# Module_Hub.net
KiCad netlist of a schematic drawn in Altium Designer
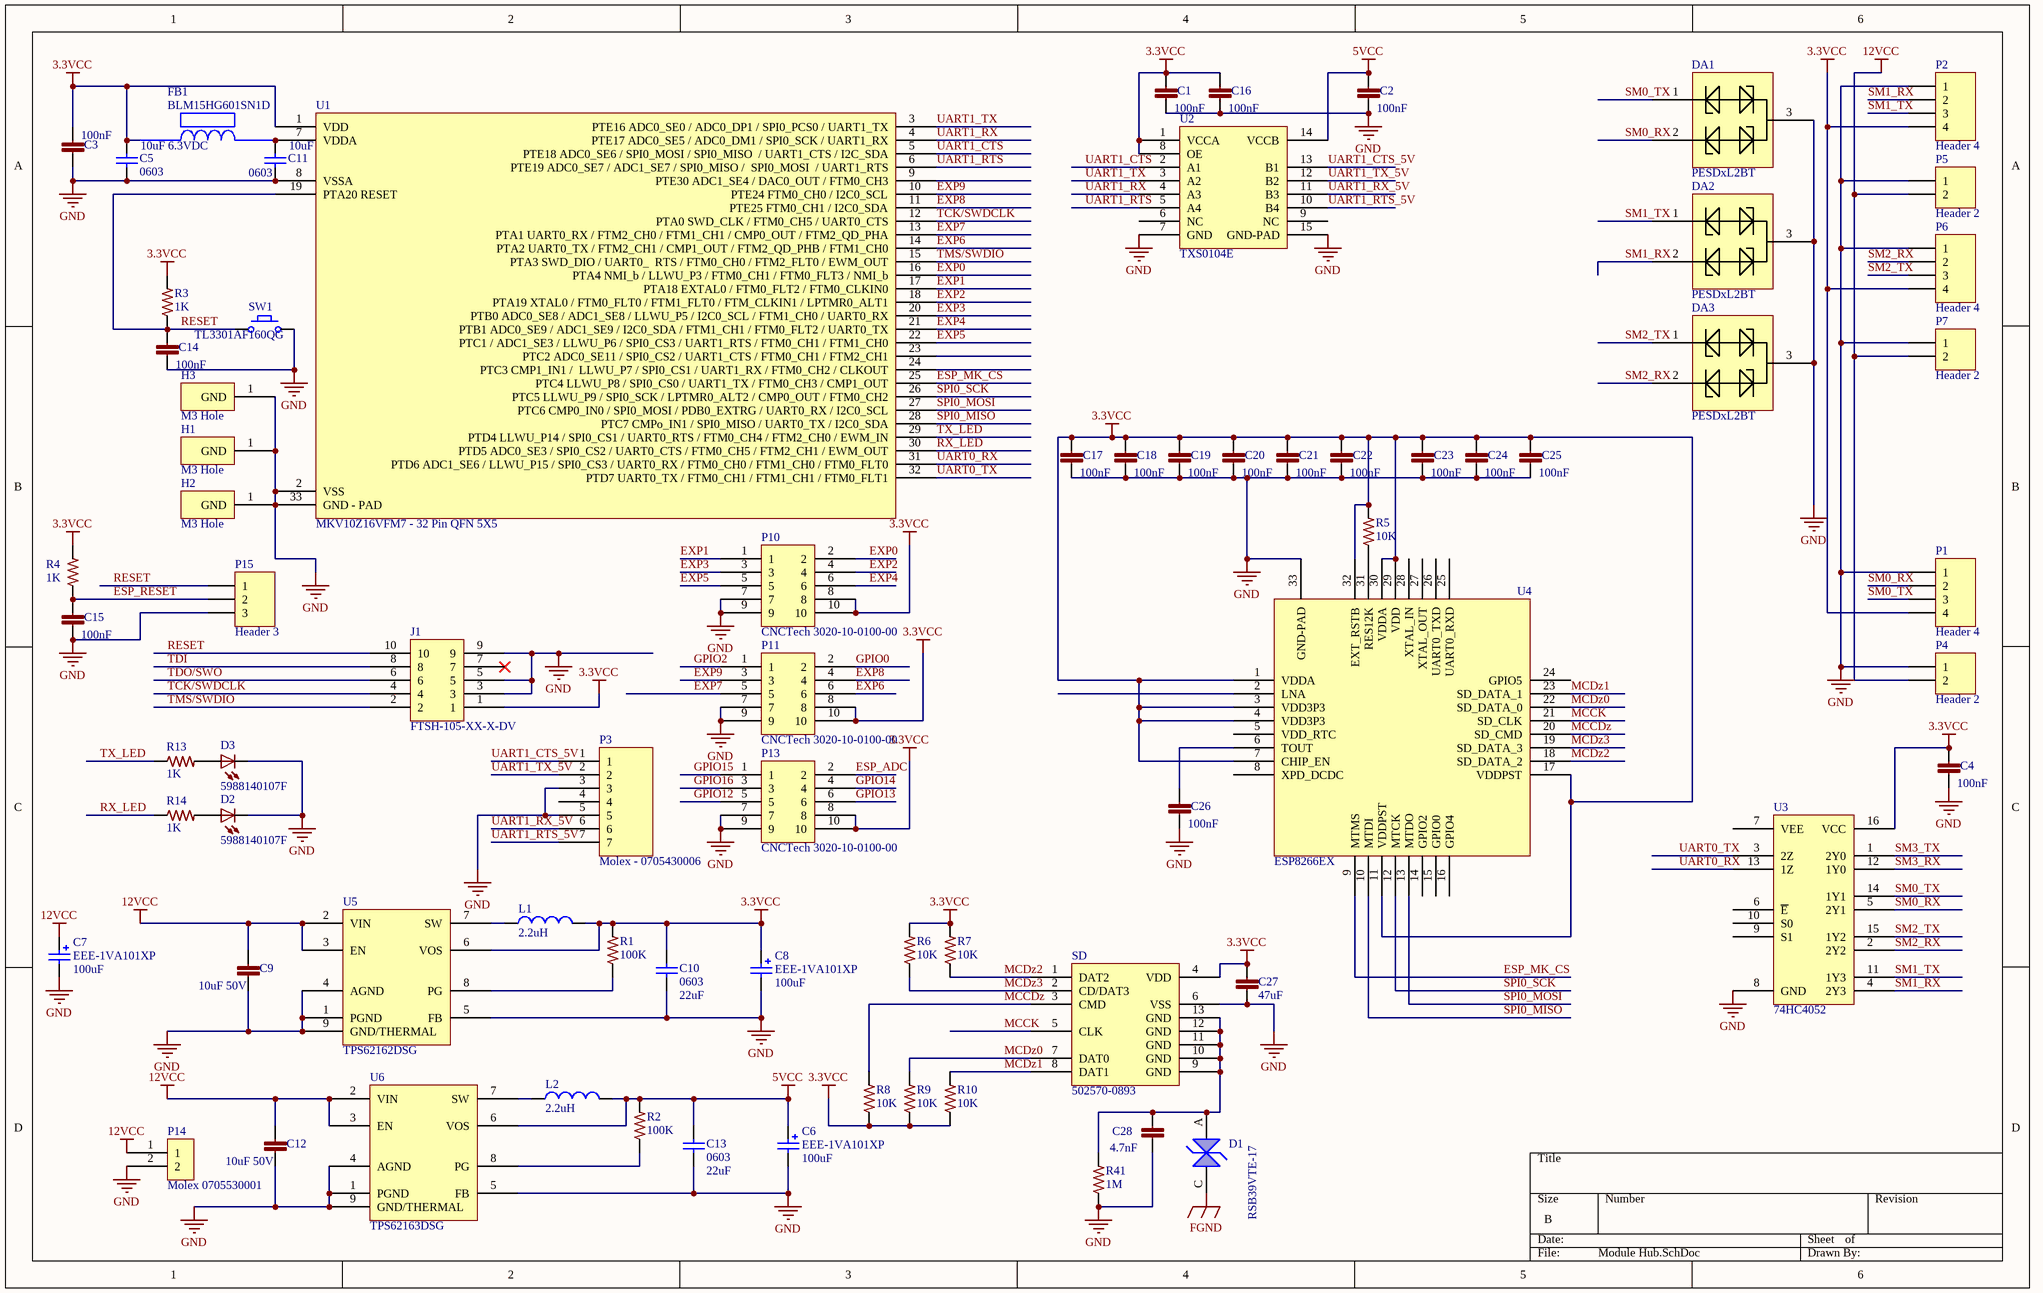
[diagram p0: Module Hub.SchDoc]

(export (version "E")
  (design (tool "Eeschema 10.0.6"))
  (components
    (comp (ref "C1")
      (value "100nF")
      (footprint "C0603")
      (description "CAP CER 0603 100nF 50V 10% X7R")
      (fields
        (field (name "MANUFACTURERPARTNUMBER") "C0603C104K5RACTU")
        (field (name "PUBLISHER") "UltiMachine")
      )
      (libsource (lib "3Delight") (part "C0603C104K5RACTU"))
    )
    (comp (ref "C2")
      (value "100nF")
      (footprint "C0603")
      (description "CAP CER 0603 100nF 50V 10% X7R")
      (fields
        (field (name "MANUFACTURERPARTNUMBER") "C0603C104K5RACTU")
        (field (name "PUBLISHER") "UltiMachine")
      )
      (libsource (lib "3Delight") (part "C0603C104K5RACTU"))
    )
    (comp (ref "C3")
      (value "100nF")
      (footprint "C0603")
      (description "CAP CER 0603 100nF 50V 10% X7R")
      (fields
        (field (name "MANUFACTURERPARTNUMBER") "C0603C104K5RACTU")
        (field (name "PUBLISHER") "UltiMachine")
      )
      (libsource (lib "3Delight") (part "C0603C104K5RACTU"))
    )
    (comp (ref "C4")
      (value "100nF")
      (footprint "C0603")
      (description "CAP CER 0603 100nF 50V 10% X7R")
      (fields
        (field (name "MANUFACTURERPARTNUMBER") "C0603C104K5RACTU")
        (field (name "PUBLISHER") "UltiMachine")
      )
      (libsource (lib "3Delight") (part "C0603C104K5RACTU"))
    )
    (comp (ref "C5")
      (value "0603")
      (footprint "C0603")
      (description "CAP CER 10UF 6.3V 10% JB 0603")
      (fields
        (field (name "MFR PART #") "C1608JB0J106K080AB")
        (field (name "MFR") "TDK")
        (field (name "ALTIUM_VALUE") "10uF 6.3VDC")
      )
      (libsource (lib "Tigershark3D") (part "C1608JB0J106K080AB"))
    )
    (comp (ref "C6")
      (value "EEE-1VA101XP")
      (footprint "EEE-1VA101XP")
      (description "CAP ALUM 100UF 35V 20% SMD")
      (fields (field (name "DIGIKEY PART #") "PCE3951CT-ND") (field (name "ALTIUM_VALUE") "100uF"))
      (libsource (lib "Tigershark3D") (part "EEE-1VA101XP"))
    )
    (comp (ref "C7")
      (value "EEE-1VA101XP")
      (footprint "EEE-1VA101XP")
      (description "CAP ALUM 100UF 35V 20% SMD")
      (fields (field (name "DIGIKEY PART #") "PCE3951CT-ND") (field (name "ALTIUM_VALUE") "100uF"))
      (libsource (lib "Tigershark3D") (part "EEE-1VA101XP"))
    )
    (comp (ref "C8")
      (value "EEE-1VA101XP")
      (footprint "EEE-1VA101XP")
      (description "CAP ALUM 100UF 35V 20% SMD")
      (fields (field (name "DIGIKEY PART #") "PCE3951CT-ND") (field (name "ALTIUM_VALUE") "100uF"))
      (libsource (lib "Tigershark3D") (part "EEE-1VA101XP"))
    )
    (comp (ref "C9")
      (value "10uF 50V")
      (footprint "C1206")
      (description "CAP CER 10UF 50V 10% X5R 1206")
      (fields
        (field (name "MANUFACTURER") "Samsung")
        (field (name "MANUFACTURERPARTNUMBER") "CL31A106KBHNNNE")
        (field (name "PUBLISHER") "UltiMachine")
      )
      (libsource (lib "Tigershark3D") (part "CL31A106KBHNNNE"))
    )
    (comp (ref "C10")
      (value "0603")
      (footprint "C0805")
      (description "CAP CER 22UF 6.3V 10% X5R 0805")
      (fields
        (field (name "MFR PART #") "CL21A226KQQNNNE")
        (field (name "MFR") "Samsung")
        (field (name "ALTIUM_VALUE") "22uF")
      )
      (libsource (lib "Sensor Package") (part "CL21A226KQQNNNE"))
    )
    (comp (ref "C11")
      (value "0603")
      (footprint "C0603")
      (description "CAP CER 10UF 6.3V 10% JB 0603")
      (fields
        (field (name "MFR PART #") "C1608JB0J106K080AB")
        (field (name "MFR") "TDK")
        (field (name "ALTIUM_VALUE") "10uF")
      )
      (libsource (lib "Tigershark3D") (part "C1608JB0J106K080AB"))
    )
    (comp (ref "C12")
      (value "10uF 50V")
      (footprint "C1206")
      (description "CAP CER 10UF 50V 10% X5R 1206")
      (fields
        (field (name "MANUFACTURER") "Samsung")
        (field (name "MANUFACTURERPARTNUMBER") "CL31A106KBHNNNE")
        (field (name "PUBLISHER") "UltiMachine")
      )
      (libsource (lib "Tigershark3D") (part "CL31A106KBHNNNE"))
    )
    (comp (ref "C13")
      (value "0603")
      (footprint "C0805")
      (description "CAP CER 22UF 6.3V 10% X5R 0805")
      (fields
        (field (name "MFR PART #") "CL21A226KQQNNNE")
        (field (name "MFR") "Samsung")
        (field (name "ALTIUM_VALUE") "22uF")
      )
      (libsource (lib "Sensor Package") (part "CL21A226KQQNNNE"))
    )
    (comp (ref "C14")
      (value "100nF")
      (footprint "C0402")
      (description "CAP CER 0402 100nF 16V 10% X7R")
      (fields
        (field (name "MANUFACTURERPARTNUMBER") "GRM155R71C104KA88D")
        (field (name "PUBLISHER") "UltiMachine")
      )
      (libsource (lib "3Delight") (part "GRM155R71C104KA88D"))
    )
    (comp (ref "C15")
      (value "100nF")
      (footprint "C0402")
      (description "CAP CER 0402 100nF 16V 10% X7R")
      (fields
        (field (name "MANUFACTURERPARTNUMBER") "GRM155R71C104KA88D")
        (field (name "PUBLISHER") "UltiMachine")
      )
      (libsource (lib "3Delight") (part "GRM155R71C104KA88D"))
    )
    (comp (ref "C16")
      (value "100nF")
      (footprint "C0603")
      (description "CAP CER 0603 100nF 50V 10% X7R")
      (fields
        (field (name "MANUFACTURERPARTNUMBER") "C0603C104K5RACTU")
        (field (name "PUBLISHER") "UltiMachine")
      )
      (libsource (lib "3Delight") (part "C0603C104K5RACTU"))
    )
    (comp (ref "C17")
      (value "100nF")
      (footprint "C0603")
      (description "CAP CER 0603 100nF 50V 10% X7R")
      (fields
        (field (name "MANUFACTURERPARTNUMBER") "C0603C104K5RACTU")
        (field (name "PUBLISHER") "UltiMachine")
      )
      (libsource (lib "3Delight") (part "C0603C104K5RACTU"))
    )
    (comp (ref "C18")
      (value "100nF")
      (footprint "C0603")
      (description "CAP CER 0603 100nF 50V 10% X7R")
      (fields
        (field (name "MANUFACTURERPARTNUMBER") "C0603C104K5RACTU")
        (field (name "PUBLISHER") "UltiMachine")
      )
      (libsource (lib "3Delight") (part "C0603C104K5RACTU"))
    )
    (comp (ref "C19")
      (value "100nF")
      (footprint "C0603")
      (description "CAP CER 0603 100nF 50V 10% X7R")
      (fields
        (field (name "MANUFACTURERPARTNUMBER") "C0603C104K5RACTU")
        (field (name "PUBLISHER") "UltiMachine")
      )
      (libsource (lib "3Delight") (part "C0603C104K5RACTU"))
    )
    (comp (ref "C20")
      (value "100nF")
      (footprint "C0603")
      (description "CAP CER 0603 100nF 50V 10% X7R")
      (fields
        (field (name "MANUFACTURERPARTNUMBER") "C0603C104K5RACTU")
        (field (name "PUBLISHER") "UltiMachine")
      )
      (libsource (lib "3Delight") (part "C0603C104K5RACTU"))
    )
    (comp (ref "C21")
      (value "100nF")
      (footprint "C0603")
      (description "CAP CER 0603 100nF 50V 10% X7R")
      (fields
        (field (name "MANUFACTURERPARTNUMBER") "C0603C104K5RACTU")
        (field (name "PUBLISHER") "UltiMachine")
      )
      (libsource (lib "3Delight") (part "C0603C104K5RACTU"))
    )
    (comp (ref "C22")
      (value "100nF")
      (footprint "C0603")
      (description "CAP CER 0603 100nF 50V 10% X7R")
      (fields
        (field (name "MANUFACTURERPARTNUMBER") "C0603C104K5RACTU")
        (field (name "PUBLISHER") "UltiMachine")
      )
      (libsource (lib "3Delight") (part "C0603C104K5RACTU"))
    )
    (comp (ref "C23")
      (value "100nF")
      (footprint "C0603")
      (description "CAP CER 0603 100nF 50V 10% X7R")
      (fields
        (field (name "MANUFACTURERPARTNUMBER") "C0603C104K5RACTU")
        (field (name "PUBLISHER") "UltiMachine")
      )
      (libsource (lib "3Delight") (part "C0603C104K5RACTU"))
    )
    (comp (ref "C24")
      (value "100nF")
      (footprint "C0603")
      (description "CAP CER 0603 100nF 50V 10% X7R")
      (fields
        (field (name "MANUFACTURERPARTNUMBER") "C0603C104K5RACTU")
        (field (name "PUBLISHER") "UltiMachine")
      )
      (libsource (lib "3Delight") (part "C0603C104K5RACTU"))
    )
    (comp (ref "C25")
      (value "100nF")
      (footprint "C0603")
      (description "CAP CER 0603 100nF 50V 10% X7R")
      (fields
        (field (name "MANUFACTURERPARTNUMBER") "C0603C104K5RACTU")
        (field (name "PUBLISHER") "UltiMachine")
      )
      (libsource (lib "3Delight") (part "C0603C104K5RACTU"))
    )
    (comp (ref "C26")
      (value "100nF")
      (footprint "C0603")
      (description "CAP CER 0603 100nF 50V 10% X7R")
      (fields
        (field (name "MANUFACTURERPARTNUMBER") "C0603C104K5RACTU")
        (field (name "PUBLISHER") "UltiMachine")
      )
      (libsource (lib "3Delight") (part "C0603C104K5RACTU"))
    )
    (comp (ref "C27")
      (value "47uF")
      (footprint "C0805")
      (description "CAP CER 47UF 6.3V 20% X5R 0805")
      (fields
        (field (name "MANUFACTURER") "Samsung")
        (field (name "MANUFACTURERPARTNUMBER") "CL21A476MQCLRNC")
        (field (name "PUBLISHER") "UltiMachine")
      )
      (libsource (lib "Tigershark3D") (part "CL21A476MQCLRNC"))
    )
    (comp (ref "C28")
      (value "4.7nF")
      (footprint "C0402")
      (description "CAP CER 0402 4.7nF 25V 10% X7R")
      (fields
        (field (name "MANUFACTURERPARTNUMBER") "CC0402KRX7R8BB472")
        (field (name "PUBLISHER") "UltiMachine")
      )
      (libsource (lib "3Delight") (part "CC0402KRX7R8BB472"))
    )
    (comp (ref "D1")
      (value "RSB39VTE-17")
      (footprint "SOD323-R")
      (description "DIODE TVS")
      (libsource (lib "3Delight") (part "RSB39VTE-17"))
    )
    (comp (ref "D2")
      (value "5988140107F")
      (footprint "LED2012120")
      (description "LED 0805 Yellow")
      (fields (field (name "PUBLISHER") "UltiMachine"))
      (libsource (lib "Tigershark3D") (part "5988140107F"))
    )
    (comp (ref "D3")
      (value "5988140107F")
      (footprint "LED2012120")
      (description "LED 0805 Yellow")
      (fields (field (name "PUBLISHER") "UltiMachine"))
      (libsource (lib "Tigershark3D") (part "5988140107F"))
    )
    (comp (ref "DA1")
      (value "PESDxL2BT")
      (footprint "SOT95P230X110-3N")
      (description "PESDxL2BT TVS Diode Array 2x")
      (libsource (lib "ZMBo Schematic Library") (part "PESDxL2BT"))
    )
    (comp (ref "DA2")
      (value "PESDxL2BT")
      (footprint "SOT95P230X110-3N")
      (description "PESDxL2BT TVS Diode Array 2x")
      (libsource (lib "ZMBo Schematic Library") (part "PESDxL2BT"))
    )
    (comp (ref "DA3")
      (value "PESDxL2BT")
      (footprint "SOT95P230X110-3N")
      (description "PESDxL2BT TVS Diode Array 2x")
      (libsource (lib "ZMBo Schematic Library") (part "PESDxL2BT"))
    )
    (comp (ref "FB1")
      (value "BLM15HG601SN1D")
      (footprint "BLM18PG121SN1D")
      (libsource (lib "AHD Part Library") (part "BLM15HG601SN1D"))
    )
    (comp (ref "H1")
      (value "M3 Hole")
      (footprint "Hole-3mm")
      (description "3mm Hole")
      (libsource (lib "Sensor Package") (part "Hole"))
    )
    (comp (ref "H2")
      (value "M3 Hole")
      (footprint "Hole-3mm")
      (description "3mm Hole")
      (libsource (lib "Sensor Package") (part "Hole"))
    )
    (comp (ref "H3")
      (value "M3 Hole")
      (footprint "Hole-3mm")
      (description "3mm Hole")
      (libsource (lib "Sensor Package") (part "Hole"))
    )
    (comp (ref "J1")
      (value "FTSH-105-XX-X-DV")
      (footprint "FTSH-105-XX-X-DV")
      (libsource (lib "Adams Altium Library") (part "ARM Cortex JTAG-DEBUG Header"))
    )
    (comp (ref "L1")
      (value "2.2uH")
      (footprint "VLS252012T-2R2M1R3")
      (description "VLS252012T-2R2M1R3")
      (fields (field (name "MFR") "TDK Corporation") (field (name "PUBLISHER") "Adam Vadala-Roth"))
      (libsource (lib "Sensor Package") (part "VLS252012T-2R2M1R3"))
    )
    (comp (ref "L2")
      (value "2.2uH")
      (footprint "VLS252012T-2R2M1R3")
      (description "VLS252012T-2R2M1R3")
      (fields (field (name "MFR") "TDK Corporation") (field (name "PUBLISHER") "Adam Vadala-Roth"))
      (libsource (lib "Sensor Package") (part "VLS252012T-2R2M1R3"))
    )
    (comp (ref "P1")
      (value "Header 4")
      (footprint "HDR1X4")
      (description "Header, 4-Pin")
      (fields (field (name "PUBLISHER") "Altium Limited"))
      (libsource (lib "Miscellaneous Connectors") (part "Header 4"))
    )
    (comp (ref "P2")
      (value "Header 4")
      (footprint "HDR1X4")
      (description "Header, 4-Pin")
      (fields (field (name "PUBLISHER") "Altium Limited"))
      (libsource (lib "Miscellaneous Connectors") (part "Header 4"))
    )
    (comp (ref "P3")
      (value "Molex - 0705430006")
      (footprint "0705530041")
      (description "0705530041")
      (fields (field (name "MFR") "Molex"))
      (libsource (lib "Sensor Package") (part "0705530041"))
    )
    (comp (ref "P4")
      (value "Header 2")
      (footprint "HDR1X2")
      (description "Header, 2-Pin")
      (fields (field (name "PUBLISHER") "Altium Limited"))
      (libsource (lib "Miscellaneous Connectors") (part "Header 2"))
    )
    (comp (ref "P5")
      (value "Header 2")
      (footprint "HDR1X2")
      (description "Header, 2-Pin")
      (fields (field (name "PUBLISHER") "Altium Limited"))
      (libsource (lib "Miscellaneous Connectors") (part "Header 2"))
    )
    (comp (ref "P6")
      (value "Header 4")
      (footprint "HDR1X4")
      (description "Header, 4-Pin")
      (fields (field (name "PUBLISHER") "Altium Limited"))
      (libsource (lib "Miscellaneous Connectors") (part "Header 4"))
    )
    (comp (ref "P7")
      (value "Header 2")
      (footprint "HDR1X2")
      (description "Header, 2-Pin")
      (fields (field (name "PUBLISHER") "Altium Limited"))
      (libsource (lib "Miscellaneous Connectors") (part "Header 2"))
    )
    (comp (ref "P10")
      (value "CNCTech 3020-10-0100-00")
      (footprint "3020-10-0100-00")
      (fields
        (field (name "MANUFACTURE PART #") "3020-10-0100-00")
        (field (name "MANUFACTURER") "CNCTech")
        (field (name "DIGIKEY PART #") "1175-1609-ND")
      )
      (libsource (lib "Tigershark3D") (part "3020-10-0100-00"))
    )
    (comp (ref "P11")
      (value "CNCTech 3020-10-0100-00")
      (footprint "3020-10-0100-00")
      (fields
        (field (name "MANUFACTURE PART #") "3020-10-0100-00")
        (field (name "MANUFACTURER") "CNCTech")
        (field (name "DIGIKEY PART #") "1175-1609-ND")
      )
      (libsource (lib "Tigershark3D") (part "3020-10-0100-00"))
    )
    (comp (ref "P13")
      (value "CNCTech 3020-10-0100-00")
      (footprint "3020-10-0100-00")
      (fields
        (field (name "MANUFACTURE PART #") "3020-10-0100-00")
        (field (name "MANUFACTURER") "CNCTech")
        (field (name "DIGIKEY PART #") "1175-1609-ND")
      )
      (libsource (lib "Tigershark3D") (part "3020-10-0100-00"))
    )
    (comp (ref "P14")
      (value "Molex 0705530001")
      (footprint "0705530001")
      (description "Molex 0705530002 Right Angle 2.54mm Shrouded Header")
      (fields (field (name "MFR") "Molex"))
      (libsource (lib "Sensor Package") (part "0705530001"))
    )
    (comp (ref "P15")
      (value "Header 3")
      (footprint "HDR1X3")
      (description "Header, 3-Pin")
      (fields (field (name "PUBLISHER") "Altium Limited"))
      (libsource (lib "Miscellaneous Connectors") (part "Header 3"))
    )
    (comp (ref "R1")
      (value "100K")
      (footprint "R0603")
      (description "RES 100K OHM 1/10W 1% 0603 SMD")
      (fields
        (field (name "MANUFACTURERPARTNUMBER") "RC0603FR-07100KL")
        (field (name "PUBLISHER") "UltiMachine")
      )
      (libsource (lib "3Delight") (part "RC0603FR-07100KL"))
    )
    (comp (ref "R2")
      (value "100K")
      (footprint "R0603")
      (description "RES 100K OHM 1/10W 1% 0603 SMD")
      (fields
        (field (name "MANUFACTURERPARTNUMBER") "RC0603FR-07100KL")
        (field (name "PUBLISHER") "UltiMachine")
      )
      (libsource (lib "3Delight") (part "RC0603FR-07100KL"))
    )
    (comp (ref "R3")
      (value "1K")
      (footprint "R0603")
      (description "RES 0603 1K 100mW 1%")
      (fields
        (field (name "MANUFACTURERPARTNUMBER") "ERJ-3EKF1001V")
        (field (name "PUBLISHER") "UltiMachine")
      )
      (libsource (lib "3Delight") (part "ERJ-3EKF1001V"))
    )
    (comp (ref "R4")
      (value "1K")
      (footprint "R0603")
      (description "RES 0603 1K 100mW 1%")
      (fields
        (field (name "MANUFACTURERPARTNUMBER") "ERJ-3EKF1001V")
        (field (name "PUBLISHER") "UltiMachine")
      )
      (libsource (lib "3Delight") (part "ERJ-3EKF1001V"))
    )
    (comp (ref "R5")
      (value "10K")
      (footprint "R0603")
      (description "RES 0603 10K 100mW 1%")
      (fields
        (field (name "MANUFACTURERPARTNUMBER") "ERJ-3EKF1002V")
        (field (name "PUBLISHER") "UltiMachine")
      )
      (libsource (lib "Tigershark3D") (part "ERJ-3EKF1002V"))
    )
    (comp (ref "R6")
      (value "10K")
      (footprint "R0603")
      (description "RES 0603 10K 100mW 1%")
      (fields
        (field (name "MANUFACTURERPARTNUMBER") "ERJ-3EKF1002V")
        (field (name "PUBLISHER") "UltiMachine")
      )
      (libsource (lib "Tigershark3D") (part "ERJ-3EKF1002V"))
    )
    (comp (ref "R7")
      (value "10K")
      (footprint "R0603")
      (description "RES 0603 10K 100mW 1%")
      (fields
        (field (name "MANUFACTURERPARTNUMBER") "ERJ-3EKF1002V")
        (field (name "PUBLISHER") "UltiMachine")
      )
      (libsource (lib "Tigershark3D") (part "ERJ-3EKF1002V"))
    )
    (comp (ref "R8")
      (value "10K")
      (footprint "R0603")
      (description "RES 0603 10K 100mW 1%")
      (fields
        (field (name "MANUFACTURERPARTNUMBER") "ERJ-3EKF1002V")
        (field (name "PUBLISHER") "UltiMachine")
      )
      (libsource (lib "Tigershark3D") (part "ERJ-3EKF1002V"))
    )
    (comp (ref "R9")
      (value "10K")
      (footprint "R0603")
      (description "RES 0603 10K 100mW 1%")
      (fields
        (field (name "MANUFACTURERPARTNUMBER") "ERJ-3EKF1002V")
        (field (name "PUBLISHER") "UltiMachine")
      )
      (libsource (lib "Tigershark3D") (part "ERJ-3EKF1002V"))
    )
    (comp (ref "R10")
      (value "10K")
      (footprint "R0603")
      (description "RES 0603 10K 100mW 1%")
      (fields
        (field (name "MANUFACTURERPARTNUMBER") "ERJ-3EKF1002V")
        (field (name "PUBLISHER") "UltiMachine")
      )
      (libsource (lib "Tigershark3D") (part "ERJ-3EKF1002V"))
    )
    (comp (ref "R13")
      (value "1K")
      (footprint "R0603")
      (description "RES 0603 1K 100mW 1%")
      (fields
        (field (name "MANUFACTURERPARTNUMBER") "ERJ-3EKF1001V")
        (field (name "PUBLISHER") "UltiMachine")
      )
      (libsource (lib "Tigershark3D") (part "ERJ-3EKF1001V"))
    )
    (comp (ref "R14")
      (value "1K")
      (footprint "R0603")
      (description "RES 0603 1K 100mW 1%")
      (fields
        (field (name "MANUFACTURERPARTNUMBER") "ERJ-3EKF1001V")
        (field (name "PUBLISHER") "UltiMachine")
      )
      (libsource (lib "Tigershark3D") (part "ERJ-3EKF1001V"))
    )
    (comp (ref "R41")
      (value "1M")
      (footprint "R0402")
      (description "RES 0402 1M 100mW 5%")
      (fields (field (name "MANUFACTURERPARTNUMBER") "ERJ2GEJ105X") (field (name "PUBLISHER") "UltiMachine"))
      (libsource (lib "3Delight") (part "ERJ2GEJ105X"))
    )
    (comp (ref "SD")
      (value "502570-0893")
      (footprint "502570-0893 - Molex SD")
      (description "microSD 502570-0893 Molex Part")
      (libsource (lib "Tigershark3D") (part "502570-0893"))
    )
    (comp (ref "SW1")
      (value "TL3301AF160QG")
      (footprint "TL3301AF160QG")
      (libsource (lib "MongoosMini") (part "TL3301AF160QG"))
    )
    (comp (ref "U1")
      (value "MKV10Z16VFM7 - 32 Pin QFN 5X5")
      (footprint "MKV10Z16VFM7")
      (description "IC MCU ARM Cortex M0+ 16KB 32QFN 75MHZ")
      (fields (field (name "MFR") "FreeScale"))
      (libsource (lib "Sensor Package") (part "MKV10Z16VFM7"))
    )
    (comp (ref "U2")
      (value "TXS0104E")
      (footprint "RGY  (S-PVQFN-N14)")
      (description "TXS0104E - Bidriectional Opendrain/pushpull level shift")
      (fields (field (name "MFR") "Texas Instruments") (field (name "MFR PART #") "TXS0104ERGYR"))
      (libsource (lib "Tigershark3D") (part "TXS0104E"))
    )
    (comp (ref "U3")
      (value "74HC4052")
      (footprint "74HC4052")
      (description "Dual 4-channel analog multiplexer/demultiplexer")
      (fields (field (name "MFR") "NXP"))
      (libsource (lib "Sensor Package") (part "74HC4052"))
    )
    (comp (ref "U4")
      (value "ESP8266EX")
      (footprint "ESP8266EX")
      (libsource (lib "Sensor Package") (part "ESP8266EX"))
    )
    (comp (ref "U5")
      (value "TPS62162DSG")
      (footprint "DSG8-1600X900TP")
      (libsource (lib "Adams Altium Library") (part "TPS62162SOP"))
    )
    (comp (ref "U6")
      (value "TPS62163DSG")
      (footprint "DSG8-1600X900TP")
      (libsource (lib "Adams Altium Library") (part "TPS62162SOP"))
    )
  )
  (nets
    (net (code "1") (name "/ESP_ADC") (class "Default")
      (node (ref "P13") (pin "2") (pinfunction "2_2") (pintype "passive"))
    )
    (net (code "2") (name "/ESP_MK_CS") (class "Default")
      (node (ref "U1") (pin "25") (pinfunction "PTC4_LLWU_P8_/_SPI0_CS0_/_UART1_TX_/_FTM0_CH3_/_CMP1_OUT_25") (pintype "passive"))
      (node (ref "U4") (pin "9") (pinfunction "MTMS_9") (pintype "passive"))
    )
    (net (code "3") (name "/ESP_RESET") (class "Default")
      (node (ref "C15") (pin "1") (pinfunction "1_1") (pintype "passive"))
      (node (ref "P15") (pin "2") (pinfunction "2_2") (pintype "passive"))
      (node (ref "R4") (pin "1") (pinfunction "1_1") (pintype "passive"))
    )
    (net (code "4") (name "/EXP0") (class "Default")
      (node (ref "P10") (pin "2") (pinfunction "2_2") (pintype "passive"))
      (node (ref "U1") (pin "16") (pinfunction "PTA4_NMI_b_/_LLWU_P3_/_FTM0_CH1_/_FTM0_FLT3_/_NMI_b_16") (pintype "passive"))
    )
    (net (code "5") (name "/EXP1") (class "Default")
      (node (ref "P10") (pin "1") (pinfunction "1_1") (pintype "passive"))
      (node (ref "U1") (pin "17") (pinfunction "PTA18_EXTAL0_/_FTM0_FLT2_/_FTM0_CLKIN0_17") (pintype "passive"))
    )
    (net (code "6") (name "/EXP2") (class "Default")
      (node (ref "P10") (pin "4") (pinfunction "4_4") (pintype "passive"))
      (node (ref "U1") (pin "18") (pinfunction "PTA19_XTAL0_/_FTM0_FLT0_/_FTM1_FLT0_/_FTM_CLKIN1_/_LPTMR0_ALT1_18") (pintype "passive"))
    )
    (net (code "7") (name "/EXP3") (class "Default")
      (node (ref "P10") (pin "3") (pinfunction "3_3") (pintype "passive"))
      (node (ref "U1") (pin "20") (pinfunction "PTB0_ADC0_SE8_/_ADC1_SE8_/_LLWU_P5_/_I2C0_SCL_/_FTM1_CH0_/_UART0_RX_20") (pintype "passive"))
    )
    (net (code "8") (name "/EXP4") (class "Default")
      (node (ref "P10") (pin "6") (pinfunction "6_6") (pintype "passive"))
      (node (ref "U1") (pin "21") (pinfunction "PTB1_ADC0_SE9_/_ADC1_SE9_/_I2C0_SDA_/_FTM1_CH1_/_FTM0_FLT2_/_UART0_TX_21") (pintype "passive"))
    )
    (net (code "9") (name "/EXP5") (class "Default")
      (node (ref "P10") (pin "5") (pinfunction "5_5") (pintype "passive"))
      (node (ref "U1") (pin "22") (pinfunction "PTC1_/_ADC1_SE3_/_LLWU_P6_/_SPI0_CS3_/_UART1_RTS_/_FTM0_CH1_/_FTM1_CH0_22") (pintype "passive"))
    )
    (net (code "10") (name "/EXP6") (class "Default")
      (node (ref "P11") (pin "6") (pinfunction "6_6") (pintype "passive"))
      (node (ref "U1") (pin "14") (pinfunction "PTA2_UART0_TX_/_FTM2_CH1_/_CMP1_OUT_/_FTM2_QD_PHB_/_FTM1_CH0_14") (pintype "passive"))
    )
    (net (code "11") (name "/EXP7") (class "Default")
      (node (ref "P11") (pin "5") (pinfunction "5_5") (pintype "passive"))
      (node (ref "U1") (pin "13") (pinfunction "PTA1_UART0_RX_/_FTM2_CH0_/_FTM1_CH1_/_CMP0_OUT_/_FTM2_QD_PHA_13") (pintype "passive"))
    )
    (net (code "12") (name "/EXP8") (class "Default")
      (node (ref "P11") (pin "4") (pinfunction "4_4") (pintype "passive"))
      (node (ref "U1") (pin "11") (pinfunction "PTE25_FTM0_CH1_/_I2C0_SDA_11") (pintype "passive"))
    )
    (net (code "13") (name "/EXP9") (class "Default")
      (node (ref "P11") (pin "3") (pinfunction "3_3") (pintype "passive"))
      (node (ref "U1") (pin "10") (pinfunction "PTE24_FTM0_CH0_/_I2C0_SCL_10") (pintype "passive"))
    )
    (net (code "14") (name "/GPIO0") (class "Default")
      (node (ref "P11") (pin "2") (pinfunction "2_2") (pintype "passive"))
    )
    (net (code "15") (name "/GPIO2") (class "Default")
      (node (ref "P11") (pin "1") (pinfunction "1_1") (pintype "passive"))
    )
    (net (code "16") (name "/GPIO12") (class "Default")
      (node (ref "P13") (pin "5") (pinfunction "5_5") (pintype "passive"))
    )
    (net (code "17") (name "/GPIO13") (class "Default")
      (node (ref "P13") (pin "6") (pinfunction "6_6") (pintype "passive"))
    )
    (net (code "18") (name "/GPIO14") (class "Default")
      (node (ref "P13") (pin "4") (pinfunction "4_4") (pintype "passive"))
    )
    (net (code "19") (name "/GPIO15") (class "Default")
      (node (ref "P13") (pin "1") (pinfunction "1_1") (pintype "passive"))
    )
    (net (code "20") (name "/GPIO16") (class "Default")
      (node (ref "P13") (pin "3") (pinfunction "3_3") (pintype "passive"))
    )
    (net (code "21") (name "/MCCDz") (class "Default")
      (node (ref "R8") (pin "2") (pinfunction "2_2") (pintype "passive"))
      (node (ref "SD") (pin "3") (pinfunction "CMD_3") (pintype "passive"))
      (node (ref "U4") (pin "20") (pinfunction "SD_CMD_20") (pintype "passive"))
    )
    (net (code "22") (name "/MCCK") (class "Default")
      (node (ref "SD") (pin "5") (pinfunction "CLK_5") (pintype "passive"))
      (node (ref "U4") (pin "21") (pinfunction "SD_CLK_21") (pintype "passive"))
    )
    (net (code "23") (name "/MCDz0") (class "Default")
      (node (ref "R9") (pin "2") (pinfunction "2_2") (pintype "passive"))
      (node (ref "SD") (pin "7") (pinfunction "DAT0_7") (pintype "passive"))
      (node (ref "U4") (pin "22") (pinfunction "SD_DATA_0_22") (pintype "passive"))
    )
    (net (code "24") (name "/MCDz1") (class "Default")
      (node (ref "R10") (pin "2") (pinfunction "2_2") (pintype "passive"))
      (node (ref "SD") (pin "8") (pinfunction "DAT1_8") (pintype "passive"))
      (node (ref "U4") (pin "23") (pinfunction "SD_DATA_1_23") (pintype "passive"))
    )
    (net (code "25") (name "/MCDz2") (class "Default")
      (node (ref "R7") (pin "1") (pinfunction "1_1") (pintype "passive"))
      (node (ref "SD") (pin "1") (pinfunction "DAT2_1") (pintype "passive"))
      (node (ref "U4") (pin "18") (pinfunction "SD_DATA_2_18") (pintype "passive"))
    )
    (net (code "26") (name "/MCDz3") (class "Default")
      (node (ref "R6") (pin "1") (pinfunction "1_1") (pintype "passive"))
      (node (ref "SD") (pin "2") (pinfunction "CD/DAT3_2") (pintype "passive"))
      (node (ref "U4") (pin "19") (pinfunction "SD_DATA_3_19") (pintype "passive"))
    )
    (net (code "27") (name "/RESET") (class "Default")
      (node (ref "C14") (pin "1") (pinfunction "1_1") (pintype "passive"))
      (node (ref "J1") (pin "10") (pinfunction "10_10") (pintype "passive"))
      (node (ref "P15") (pin "1") (pinfunction "1_1") (pintype "passive"))
      (node (ref "R3") (pin "1") (pinfunction "1_1") (pintype "passive"))
      (node (ref "SW1") (pin "1") (pintype "passive"))
      (node (ref "U1") (pin "19") (pinfunction "PTA20_RESET_19") (pintype "passive"))
    )
    (net (code "28") (name "/RX_LED") (class "Default")
      (node (ref "R14") (pin "1") (pinfunction "1_1") (pintype "passive"))
      (node (ref "U1") (pin "30") (pinfunction "PTD5_ADC0_SE3_/_SPI0_CS2_/_UART0_CTS_/_FTM0_CH5_/_FTM2_CH1_/_EWM_OUT_30") (pintype "passive"))
    )
    (net (code "29") (name "/SM0_RX") (class "Default")
      (node (ref "DA1") (pin "2") (pinfunction "2_2") (pintype "passive"))
      (node (ref "P1") (pin "2") (pinfunction "2_2") (pintype "passive"))
      (node (ref "U3") (pin "5") (pinfunction "2Y1_5") (pintype "passive"))
    )
    (net (code "30") (name "/SM0_TX") (class "Default")
      (node (ref "DA1") (pin "1") (pinfunction "1_1") (pintype "passive"))
      (node (ref "P1") (pin "3") (pinfunction "3_3") (pintype "passive"))
      (node (ref "U3") (pin "14") (pinfunction "1Y1_14") (pintype "passive"))
    )
    (net (code "31") (name "/SM1_RX") (class "Default")
      (node (ref "DA2") (pin "2") (pinfunction "2_2") (pintype "passive"))
      (node (ref "P2") (pin "2") (pinfunction "2_2") (pintype "passive"))
      (node (ref "U3") (pin "4") (pinfunction "2Y3_4") (pintype "passive"))
    )
    (net (code "32") (name "/SM1_TX") (class "Default")
      (node (ref "DA2") (pin "1") (pinfunction "1_1") (pintype "passive"))
      (node (ref "P2") (pin "3") (pinfunction "3_3") (pintype "passive"))
      (node (ref "U3") (pin "11") (pinfunction "1Y3_11") (pintype "passive"))
    )
    (net (code "33") (name "/SM2_RX") (class "Default")
      (node (ref "DA3") (pin "2") (pinfunction "2_2") (pintype "passive"))
      (node (ref "P6") (pin "2") (pinfunction "2_2") (pintype "passive"))
      (node (ref "U3") (pin "2") (pinfunction "2Y2_2") (pintype "passive"))
    )
    (net (code "34") (name "/SM2_TX") (class "Default")
      (node (ref "DA3") (pin "1") (pinfunction "1_1") (pintype "passive"))
      (node (ref "P6") (pin "3") (pinfunction "3_3") (pintype "passive"))
      (node (ref "U3") (pin "15") (pinfunction "1Y2_15") (pintype "passive"))
    )
    (net (code "35") (name "/SM3_RX") (class "Default")
      (node (ref "U3") (pin "12") (pinfunction "1Y0_12") (pintype "passive"))
    )
    (net (code "36") (name "/SM3_TX") (class "Default")
      (node (ref "U3") (pin "1") (pinfunction "2Y0_1") (pintype "passive"))
    )
    (net (code "37") (name "/SPI0_MISO") (class "Default")
      (node (ref "U1") (pin "28") (pinfunction "PTC7_CMPo_IN1_/_SPI0_MISO_/_UART0_TX_/_I2C0_SDA_28") (pintype "passive"))
      (node (ref "U4") (pin "10") (pinfunction "MTDI_10") (pintype "passive"))
    )
    (net (code "38") (name "/SPI0_MOSI") (class "Default")
      (node (ref "U1") (pin "27") (pinfunction "PTC6_CMP0_IN0_/_SPI0_MOSI_/_PDB0_EXTRG_/_UART0_RX_/_I2C0_SCL_27") (pintype "passive"))
      (node (ref "U4") (pin "13") (pinfunction "MTDO_13") (pintype "passive"))
    )
    (net (code "39") (name "/SPI0_SCK") (class "Default")
      (node (ref "U1") (pin "26") (pinfunction "PTC5_LLWU_P9_/_SPI0_SCK_/_LPTMR0_ALT2_/_CMP0_OUT_/_FTM0_CH2_26") (pintype "passive"))
      (node (ref "U4") (pin "12") (pinfunction "MTCK_12") (pintype "passive"))
    )
    (net (code "40") (name "/TCK{slash}SWDCLK") (class "Default")
      (node (ref "J1") (pin "4") (pinfunction "4_4") (pintype "passive"))
      (node (ref "U1") (pin "12") (pinfunction "PTA0_SWD_CLK_/_FTM0_CH5_/_UART0_CTS_12") (pintype "passive"))
    )
    (net (code "41") (name "/TDI") (class "Default")
      (node (ref "J1") (pin "8") (pinfunction "8_8") (pintype "passive"))
    )
    (net (code "42") (name "/TDO{slash}SWO") (class "Default")
      (node (ref "J1") (pin "6") (pinfunction "6_6") (pintype "passive"))
    )
    (net (code "43") (name "/TMS{slash}SWDIO") (class "Default")
      (node (ref "J1") (pin "2") (pinfunction "2_2") (pintype "passive"))
      (node (ref "U1") (pin "15") (pinfunction "PTA3_SWD_DIO_/_UART0___RTS_/_FTM0_CH0_/_FTM2_FLT0_/_EWM_OUT_15") (pintype "passive"))
    )
    (net (code "44") (name "/TX_LED") (class "Default")
      (node (ref "R13") (pin "1") (pinfunction "1_1") (pintype "passive"))
      (node (ref "U1") (pin "29") (pinfunction "PTD4_LLWU_P14_/_SPI0_CS1_/_UART0_RTS_/_FTM0_CH4_/_FTM2_CH0_/_EWM_IN_29") (pintype "passive"))
    )
    (net (code "45") (name "/UART0_RX") (class "Default")
      (node (ref "U1") (pin "31") (pinfunction "PTD6_ADC1_SE6_/_LLWU_P15_/_SPI0_CS3_/_UART0_RX_/_FTM0_CH0_/_FTM1_CH0_/_FTM0_FLT0_31") (pintype "passive"))
      (node (ref "U3") (pin "13") (pinfunction "1Z_13") (pintype "passive"))
    )
    (net (code "46") (name "/UART0_TX") (class "Default")
      (node (ref "U1") (pin "32") (pinfunction "PTD7_UART0_TX_/_FTM0_CH1_/_FTM1_CH1_/_FTM0_FLT1_32") (pintype "passive"))
      (node (ref "U3") (pin "3") (pinfunction "2Z_3") (pintype "passive"))
    )
    (net (code "47") (name "/UART1_CTS") (class "Default")
      (node (ref "U1") (pin "5") (pinfunction "PTE18_ADC0_SE6_/_SPI0_MOSI_/_SPI0_MISO__/_UART1_CTS_/_I2C_SDA_5") (pintype "passive"))
      (node (ref "U2") (pin "2") (pinfunction "A1_2") (pintype "passive"))
    )
    (net (code "48") (name "/UART1_CTS_5V") (class "Default")
      (node (ref "P3") (pin "1") (pinfunction "1_1") (pintype "passive"))
      (node (ref "U2") (pin "13") (pinfunction "B1_13") (pintype "passive"))
    )
    (net (code "49") (name "/UART1_RTS") (class "Default")
      (node (ref "U1") (pin "6") (pinfunction "PTE19_ADC0_SE7_/_ADC1_SE7_/_SPI0_MISO_/__SPI0_MOSI__/_UART1_RTS_6") (pintype "passive"))
      (node (ref "U2") (pin "5") (pinfunction "A4_5") (pintype "passive"))
    )
    (net (code "50") (name "/UART1_RTS_5V") (class "Default")
      (node (ref "P3") (pin "7") (pinfunction "7_7") (pintype "passive"))
      (node (ref "U2") (pin "10") (pinfunction "B4_10") (pintype "passive"))
    )
    (net (code "51") (name "/UART1_RX") (class "Default")
      (node (ref "U1") (pin "4") (pinfunction "PTE17_ADC0_SE5_/_ADC0_DM1_/_SPI0_SCK_/_UART1_RX_4") (pintype "passive"))
      (node (ref "U2") (pin "4") (pinfunction "A3_4") (pintype "passive"))
    )
    (net (code "52") (name "/UART1_RX_5V") (class "Default")
      (node (ref "P3") (pin "6") (pinfunction "6_6") (pintype "passive"))
      (node (ref "U2") (pin "11") (pinfunction "B3_11") (pintype "passive"))
    )
    (net (code "53") (name "/UART1_TX") (class "Default")
      (node (ref "U1") (pin "3") (pinfunction "PTE16_ADC0_SE0_/_ADC0_DP1_/_SPI0_PCS0_/_UART1_TX_3") (pintype "passive"))
      (node (ref "U2") (pin "3") (pinfunction "A2_3") (pintype "passive"))
    )
    (net (code "54") (name "/UART1_TX_5V") (class "Default")
      (node (ref "P3") (pin "2") (pinfunction "2_2") (pintype "passive"))
      (node (ref "U2") (pin "12") (pinfunction "B2_12") (pintype "passive"))
    )
    (net (code "55") (name "3.3VCC") (class "Default")
      (node (ref "C1") (pin "1") (pinfunction "1_1") (pintype "passive"))
      (node (ref "C10") (pin "2") (pinfunction "2_2") (pintype "passive"))
      (node (ref "C16") (pin "1") (pinfunction "1_1") (pintype "passive"))
      (node (ref "C17") (pin "1") (pinfunction "1_1") (pintype "passive"))
      (node (ref "C18") (pin "1") (pinfunction "1_1") (pintype "passive"))
      (node (ref "C19") (pin "1") (pinfunction "1_1") (pintype "passive"))
      (node (ref "C20") (pin "1") (pinfunction "1_1") (pintype "passive"))
      (node (ref "C21") (pin "1") (pinfunction "1_1") (pintype "passive"))
      (node (ref "C22") (pin "1") (pinfunction "1_1") (pintype "passive"))
      (node (ref "C23") (pin "1") (pinfunction "1_1") (pintype "passive"))
      (node (ref "C24") (pin "1") (pinfunction "1_1") (pintype "passive"))
      (node (ref "C25") (pin "1") (pinfunction "1_1") (pintype "passive"))
      (node (ref "C27") (pin "1") (pinfunction "1_1") (pintype "passive"))
      (node (ref "C3") (pin "1") (pinfunction "1_1") (pintype "passive"))
      (node (ref "C4") (pin "1") (pinfunction "1_1") (pintype "passive"))
      (node (ref "C5") (pin "2") (pinfunction "2_2") (pintype "passive"))
      (node (ref "C8") (pin "1") (pinfunction "1_1") (pintype "passive"))
      (node (ref "FB1") (pin "1") (pinfunction "1_1") (pintype "passive"))
      (node (ref "J1") (pin "1") (pinfunction "1_1") (pintype "passive"))
      (node (ref "L1") (pin "2") (pinfunction "2_2") (pintype "passive"))
      (node (ref "P1") (pin "4") (pinfunction "4_4") (pintype "passive"))
      (node (ref "P10") (pin "10") (pinfunction "10_10") (pintype "passive"))
      (node (ref "P10") (pin "8") (pinfunction "8_8") (pintype "passive"))
      (node (ref "P11") (pin "10") (pinfunction "10_10") (pintype "passive"))
      (node (ref "P11") (pin "8") (pinfunction "8_8") (pintype "passive"))
      (node (ref "P13") (pin "10") (pinfunction "10_10") (pintype "passive"))
      (node (ref "P13") (pin "8") (pinfunction "8_8") (pintype "passive"))
      (node (ref "P2") (pin "4") (pinfunction "4_4") (pintype "passive"))
      (node (ref "P6") (pin "4") (pinfunction "4_4") (pintype "passive"))
      (node (ref "R1") (pin "2") (pinfunction "2_2") (pintype "passive"))
      (node (ref "R10") (pin "1") (pinfunction "1_1") (pintype "passive"))
      (node (ref "R3") (pin "2") (pinfunction "2_2") (pintype "passive"))
      (node (ref "R4") (pin "2") (pinfunction "2_2") (pintype "passive"))
      (node (ref "R5") (pin "2") (pinfunction "2_2") (pintype "passive"))
      (node (ref "R6") (pin "2") (pinfunction "2_2") (pintype "passive"))
      (node (ref "R7") (pin "2") (pinfunction "2_2") (pintype "passive"))
      (node (ref "R8") (pin "1") (pinfunction "1_1") (pintype "passive"))
      (node (ref "R9") (pin "1") (pinfunction "1_1") (pintype "passive"))
      (node (ref "SD") (pin "4") (pinfunction "VDD_4") (pintype "passive"))
      (node (ref "U1") (pin "1") (pinfunction "VDD_1") (pintype "passive"))
      (node (ref "U2") (pin "1") (pinfunction "VCCA_1") (pintype "passive"))
      (node (ref "U2") (pin "8") (pinfunction "OE_8") (pintype "passive"))
      (node (ref "U3") (pin "16") (pinfunction "VCC_16") (pintype "passive"))
      (node (ref "U4") (pin "1") (pinfunction "VDDA_1") (pintype "passive"))
      (node (ref "U4") (pin "11") (pinfunction "VDDPST_11") (pintype "passive"))
      (node (ref "U4") (pin "17") (pinfunction "VDDPST_17") (pintype "passive"))
      (node (ref "U4") (pin "29") (pinfunction "VDD_29") (pintype "passive"))
      (node (ref "U4") (pin "3") (pinfunction "VDD3P3_3") (pintype "passive"))
      (node (ref "U4") (pin "30") (pinfunction "VDDA_30") (pintype "passive"))
      (node (ref "U4") (pin "32") (pinfunction "EXT_RSTB_32") (pintype "passive"))
      (node (ref "U4") (pin "4") (pinfunction "VDD3P3_4") (pintype "passive"))
      (node (ref "U4") (pin "7") (pinfunction "CHIP_EN_7") (pintype "passive"))
      (node (ref "U5") (pin "6") (pinfunction "VOS_6") (pintype "passive"))
    )
    (net (code "56") (name "5VCC") (class "Default")
      (node (ref "C13") (pin "2") (pinfunction "2_2") (pintype "passive"))
      (node (ref "C2") (pin "1") (pinfunction "1_1") (pintype "passive"))
      (node (ref "C6") (pin "1") (pinfunction "1_1") (pintype "passive"))
      (node (ref "L2") (pin "2") (pinfunction "2_2") (pintype "passive"))
      (node (ref "R2") (pin "2") (pinfunction "2_2") (pintype "passive"))
      (node (ref "U2") (pin "14") (pinfunction "VCCB_14") (pintype "passive"))
      (node (ref "U6") (pin "6") (pinfunction "VOS_6") (pintype "passive"))
    )
    (net (code "57") (name "12VCC") (class "Default")
      (node (ref "C12") (pin "1") (pinfunction "1_1") (pintype "passive"))
      (node (ref "C7") (pin "1") (pinfunction "1_1") (pintype "passive"))
      (node (ref "C9") (pin "1") (pinfunction "1_1") (pintype "passive"))
      (node (ref "P14") (pin "1") (pinfunction "1_1") (pintype "passive"))
      (node (ref "P4") (pin "2") (pinfunction "2_2") (pintype "passive"))
      (node (ref "P5") (pin "2") (pinfunction "2_2") (pintype "passive"))
      (node (ref "P7") (pin "2") (pinfunction "2_2") (pintype "passive"))
      (node (ref "U5") (pin "2") (pinfunction "VIN_2") (pintype "passive"))
      (node (ref "U5") (pin "3") (pinfunction "EN_3") (pintype "passive"))
      (node (ref "U6") (pin "2") (pinfunction "VIN_2") (pintype "passive"))
      (node (ref "U6") (pin "3") (pinfunction "EN_3") (pintype "passive"))
    )
    (net (code "58") (name "FGND") (class "Default")
      (node (ref "D1") (pin "C") (pinfunction "C_C") (pintype "power_in"))
    )
    (net (code "59") (name "GND") (class "Default")
      (node (ref "C1") (pin "2") (pinfunction "2_2") (pintype "passive"))
      (node (ref "C10") (pin "1") (pinfunction "1_1") (pintype "passive"))
      (node (ref "C11") (pin "1") (pinfunction "1_1") (pintype "passive"))
      (node (ref "C12") (pin "2") (pinfunction "2_2") (pintype "passive"))
      (node (ref "C13") (pin "1") (pinfunction "1_1") (pintype "passive"))
      (node (ref "C14") (pin "2") (pinfunction "2_2") (pintype "passive"))
      (node (ref "C15") (pin "2") (pinfunction "2_2") (pintype "passive"))
      (node (ref "C16") (pin "2") (pinfunction "2_2") (pintype "passive"))
      (node (ref "C17") (pin "2") (pinfunction "2_2") (pintype "passive"))
      (node (ref "C18") (pin "2") (pinfunction "2_2") (pintype "passive"))
      (node (ref "C19") (pin "2") (pinfunction "2_2") (pintype "passive"))
      (node (ref "C2") (pin "2") (pinfunction "2_2") (pintype "passive"))
      (node (ref "C20") (pin "2") (pinfunction "2_2") (pintype "passive"))
      (node (ref "C21") (pin "2") (pinfunction "2_2") (pintype "passive"))
      (node (ref "C22") (pin "2") (pinfunction "2_2") (pintype "passive"))
      (node (ref "C23") (pin "2") (pinfunction "2_2") (pintype "passive"))
      (node (ref "C24") (pin "2") (pinfunction "2_2") (pintype "passive"))
      (node (ref "C25") (pin "2") (pinfunction "2_2") (pintype "passive"))
      (node (ref "C26") (pin "2") (pinfunction "2_2") (pintype "passive"))
      (node (ref "C27") (pin "2") (pinfunction "2_2") (pintype "passive"))
      (node (ref "C28") (pin "2") (pinfunction "2_2") (pintype "passive"))
      (node (ref "C3") (pin "2") (pinfunction "2_2") (pintype "passive"))
      (node (ref "C4") (pin "2") (pinfunction "2_2") (pintype "passive"))
      (node (ref "C5") (pin "1") (pinfunction "1_1") (pintype "passive"))
      (node (ref "C6") (pin "2") (pinfunction "2_2") (pintype "passive"))
      (node (ref "C7") (pin "2") (pinfunction "2_2") (pintype "passive"))
      (node (ref "C8") (pin "2") (pinfunction "2_2") (pintype "passive"))
      (node (ref "C9") (pin "2") (pinfunction "2_2") (pintype "passive"))
      (node (ref "D2") (pin "C") (pinfunction "C_C") (pintype "passive"))
      (node (ref "D3") (pin "C") (pinfunction "C_C") (pintype "passive"))
      (node (ref "DA1") (pin "3") (pinfunction "3_3") (pintype "passive"))
      (node (ref "DA2") (pin "3") (pinfunction "3_3") (pintype "passive"))
      (node (ref "DA3") (pin "3") (pinfunction "3_3") (pintype "passive"))
      (node (ref "H1") (pin "1") (pinfunction "GND_1") (pintype "passive"))
      (node (ref "H2") (pin "1") (pinfunction "GND_1") (pintype "passive"))
      (node (ref "H3") (pin "1") (pinfunction "GND_1") (pintype "passive"))
      (node (ref "J1") (pin "3") (pinfunction "3_3") (pintype "passive"))
      (node (ref "J1") (pin "5") (pinfunction "5_5") (pintype "passive"))
      (node (ref "J1") (pin "9") (pinfunction "9_9") (pintype "passive"))
      (node (ref "P1") (pin "1") (pinfunction "1_1") (pintype "passive"))
      (node (ref "P10") (pin "7") (pinfunction "7_7") (pintype "passive"))
      (node (ref "P10") (pin "9") (pinfunction "9_9") (pintype "passive"))
      (node (ref "P11") (pin "7") (pinfunction "7_7") (pintype "passive"))
      (node (ref "P11") (pin "9") (pinfunction "9_9") (pintype "passive"))
      (node (ref "P13") (pin "7") (pinfunction "7_7") (pintype "passive"))
      (node (ref "P13") (pin "9") (pinfunction "9_9") (pintype "passive"))
      (node (ref "P14") (pin "2") (pinfunction "2_2") (pintype "passive"))
      (node (ref "P15") (pin "3") (pinfunction "3_3") (pintype "passive"))
      (node (ref "P2") (pin "1") (pinfunction "1_1") (pintype "passive"))
      (node (ref "P3") (pin "3") (pinfunction "3_3") (pintype "passive"))
      (node (ref "P3") (pin "5") (pinfunction "5_5") (pintype "passive"))
      (node (ref "P4") (pin "1") (pinfunction "1_1") (pintype "passive"))
      (node (ref "P5") (pin "1") (pinfunction "1_1") (pintype "passive"))
      (node (ref "P6") (pin "1") (pinfunction "1_1") (pintype "passive"))
      (node (ref "P7") (pin "1") (pinfunction "1_1") (pintype "passive"))
      (node (ref "R41") (pin "1") (pinfunction "1_1") (pintype "passive"))
      (node (ref "SD") (pin "6") (pinfunction "VSS_6") (pintype "passive"))
      (node (ref "SW1") (pin "2") (pintype "passive"))
      (node (ref "U1") (pin "2") (pinfunction "VSS_2") (pintype "passive"))
      (node (ref "U1") (pin "33") (pinfunction "GND_-_PAD_33") (pintype "passive"))
      (node (ref "U1") (pin "8") (pinfunction "VSSA_8") (pintype "passive"))
      (node (ref "U2") (pin "15") (pinfunction "GND-PAD_15") (pintype "passive"))
      (node (ref "U2") (pin "7") (pinfunction "GND_7") (pintype "passive"))
      (node (ref "U3") (pin "8") (pinfunction "GND_8") (pintype "passive"))
      (node (ref "U4") (pin "33") (pinfunction "GND-PAD_33") (pintype "passive"))
      (node (ref "U5") (pin "1") (pinfunction "PGND_1") (pintype "passive"))
      (node (ref "U5") (pin "4") (pinfunction "AGND_4") (pintype "passive"))
      (node (ref "U5") (pin "5") (pinfunction "FB_5") (pintype "passive"))
      (node (ref "U5") (pin "9") (pinfunction "GND/THERMAL_9") (pintype "passive"))
      (node (ref "U6") (pin "1") (pinfunction "PGND_1") (pintype "passive"))
      (node (ref "U6") (pin "4") (pinfunction "AGND_4") (pintype "passive"))
      (node (ref "U6") (pin "5") (pinfunction "FB_5") (pintype "passive"))
      (node (ref "U6") (pin "9") (pinfunction "GND/THERMAL_9") (pintype "passive"))
    )
    (net (code "60") (name "Net-(C28-Pad1)") (class "Default")
      (node (ref "C28") (pin "1") (pinfunction "1_1") (pintype "passive"))
      (node (ref "D1") (pin "A") (pinfunction "A_A") (pintype "power_in"))
      (node (ref "R41") (pin "2") (pinfunction "2_2") (pintype "passive"))
      (node (ref "SD") (pin "10") (pinfunction "GND_10") (pintype "passive"))
      (node (ref "SD") (pin "11") (pinfunction "GND_11") (pintype "passive"))
      (node (ref "SD") (pin "12") (pinfunction "GND_12") (pintype "passive"))
      (node (ref "SD") (pin "13") (pinfunction "GND_13") (pintype "passive"))
      (node (ref "SD") (pin "9") (pinfunction "GND_9") (pintype "passive"))
    )
    (net (code "61") (name "Net-(D2-PadA)") (class "Default")
      (node (ref "D2") (pin "A") (pinfunction "A_A") (pintype "passive"))
      (node (ref "R14") (pin "2") (pinfunction "2_2") (pintype "passive"))
    )
    (net (code "62") (name "Net-(D3-PadA)") (class "Default")
      (node (ref "D3") (pin "A") (pinfunction "A_A") (pintype "passive"))
      (node (ref "R13") (pin "2") (pinfunction "2_2") (pintype "passive"))
    )
    (net (code "63") (name "Net-(U1-VDDA)") (class "Default")
      (node (ref "C11") (pin "2") (pinfunction "2_2") (pintype "passive"))
      (node (ref "FB1") (pin "2") (pinfunction "2_2") (pintype "passive"))
      (node (ref "U1") (pin "7") (pinfunction "VDDA_7") (pintype "passive"))
    )
    (net (code "64") (name "Net-(U4-RES12K)") (class "Default")
      (node (ref "R5") (pin "1") (pinfunction "1_1") (pintype "passive"))
      (node (ref "U4") (pin "31") (pinfunction "RES12K_31") (pintype "passive"))
    )
    (net (code "65") (name "Net-(U4-TOUT)") (class "Default")
      (node (ref "C26") (pin "1") (pinfunction "1_1") (pintype "passive"))
      (node (ref "U4") (pin "6") (pinfunction "TOUT_6") (pintype "passive"))
    )
    (net (code "66") (name "Net-(U5-PG)") (class "Default")
      (node (ref "R1") (pin "1") (pinfunction "1_1") (pintype "passive"))
      (node (ref "U5") (pin "8") (pinfunction "PG_8") (pintype "passive"))
    )
    (net (code "67") (name "Net-(U5-SW)") (class "Default")
      (node (ref "L1") (pin "1") (pinfunction "1_1") (pintype "passive"))
      (node (ref "U5") (pin "7") (pinfunction "SW_7") (pintype "passive"))
    )
    (net (code "68") (name "Net-(U6-PG)") (class "Default")
      (node (ref "R2") (pin "1") (pinfunction "1_1") (pintype "passive"))
      (node (ref "U6") (pin "8") (pinfunction "PG_8") (pintype "passive"))
    )
    (net (code "69") (name "Net-(U6-SW)") (class "Default")
      (node (ref "L2") (pin "1") (pinfunction "1_1") (pintype "passive"))
      (node (ref "U6") (pin "7") (pinfunction "SW_7") (pintype "passive"))
    )
    (net (code "70") (name "unconnected-(J1-Pad7)") (class "Default")
      (node (ref "J1") (pin "7") (pinfunction "7_7") (pintype "passive+no_connect"))
    )
    (net (code "71") (name "unconnected-(P3-Pad4)") (class "Default")
      (node (ref "P3") (pin "4") (pinfunction "4_4") (pintype "passive"))
    )
    (net (code "72") (name "unconnected-(U1-PTC2_ADC0_SE11_{slash}_SPI0_CS2_{slash}_UART1_CTS_{slash}_FTM0_CH1_{slash}_FTM2_CH1-Pad23)") (class "Default")
      (node (ref "U1") (pin "23") (pinfunction "PTC2_ADC0_SE11_/_SPI0_CS2_/_UART1_CTS_/_FTM0_CH1_/_FTM2_CH1_23") (pintype "passive"))
    )
    (net (code "73") (name "unconnected-(U1-PTC3_CMP1_IN1_{slash}__LLWU_P7_{slash}_SPI0_CS1_{slash}_UART1_RX_{slash}_FTM0_CH2_{slash}_CLKOUT-Pad24)") (class "Default")
      (node (ref "U1") (pin "24") (pinfunction "PTC3_CMP1_IN1_/__LLWU_P7_/_SPI0_CS1_/_UART1_RX_/_FTM0_CH2_/_CLKOUT_24") (pintype "passive"))
    )
    (net (code "74") (name "unconnected-(U1-PTE30_ADC1_SE4_{slash}_DAC0_OUT_{slash}_FTM0_CH3-Pad9)") (class "Default")
      (node (ref "U1") (pin "9") (pinfunction "PTE30_ADC1_SE4_/_DAC0_OUT_/_FTM0_CH3_9") (pintype "passive"))
    )
    (net (code "75") (name "unconnected-(U2-NC-Pad6)") (class "Default")
      (node (ref "U2") (pin "6") (pinfunction "NC_6") (pintype "passive"))
    )
    (net (code "76") (name "unconnected-(U2-NC-Pad9)") (class "Default")
      (node (ref "U2") (pin "9") (pinfunction "NC_9") (pintype "passive"))
    )
    (net (code "77") (name "unconnected-(U3-S0-Pad10)") (class "Default")
      (node (ref "U3") (pin "10") (pinfunction "S0_10") (pintype "passive"))
    )
    (net (code "78") (name "unconnected-(U3-S1-Pad9)") (class "Default")
      (node (ref "U3") (pin "9") (pinfunction "S1_9") (pintype "passive"))
    )
    (net (code "79") (name "unconnected-(U3-VEE-Pad7)") (class "Default")
      (node (ref "U3") (pin "7") (pinfunction "VEE_7") (pintype "passive"))
    )
    (net (code "80") (name "unconnected-(U3-~{E}-Pad6)") (class "Default")
      (node (ref "U3") (pin "6") (pinfunction "~{E}_6") (pintype "passive"))
    )
    (net (code "81") (name "unconnected-(U4-GPIO0-Pad15)") (class "Default")
      (node (ref "U4") (pin "15") (pinfunction "GPIO0_15") (pintype "passive"))
    )
    (net (code "82") (name "unconnected-(U4-GPIO2-Pad14)") (class "Default")
      (node (ref "U4") (pin "14") (pinfunction "GPIO2_14") (pintype "passive"))
    )
    (net (code "83") (name "unconnected-(U4-GPIO4-Pad16)") (class "Default")
      (node (ref "U4") (pin "16") (pinfunction "GPIO4_16") (pintype "passive"))
    )
    (net (code "84") (name "unconnected-(U4-GPIO5-Pad24)") (class "Default")
      (node (ref "U4") (pin "24") (pinfunction "GPIO5_24") (pintype "passive"))
    )
    (net (code "85") (name "unconnected-(U4-LNA-Pad2)") (class "Default")
      (node (ref "U4") (pin "2") (pinfunction "LNA_2") (pintype "passive"))
    )
    (net (code "86") (name "unconnected-(U4-UART0_RXD-Pad25)") (class "Default")
      (node (ref "U4") (pin "25") (pinfunction "UART0_RXD_25") (pintype "passive"))
    )
    (net (code "87") (name "unconnected-(U4-UART0_TXD-Pad26)") (class "Default")
      (node (ref "U4") (pin "26") (pinfunction "UART0_TXD_26") (pintype "passive"))
    )
    (net (code "88") (name "unconnected-(U4-VDD_RTC-Pad5)") (class "Default")
      (node (ref "U4") (pin "5") (pinfunction "VDD_RTC_5") (pintype "passive"))
    )
    (net (code "89") (name "unconnected-(U4-XPD_DCDC-Pad8)") (class "Default")
      (node (ref "U4") (pin "8") (pinfunction "XPD_DCDC_8") (pintype "passive"))
    )
    (net (code "90") (name "unconnected-(U4-XTAL_IN-Pad28)") (class "Default")
      (node (ref "U4") (pin "28") (pinfunction "XTAL_IN_28") (pintype "passive"))
    )
    (net (code "91") (name "unconnected-(U4-XTAL_OUT-Pad27)") (class "Default")
      (node (ref "U4") (pin "27") (pinfunction "XTAL_OUT_27") (pintype "passive"))
    )
  )
)
